# nuc972_power.net
KiCad netlist of a schematic drawn in Altium Designer
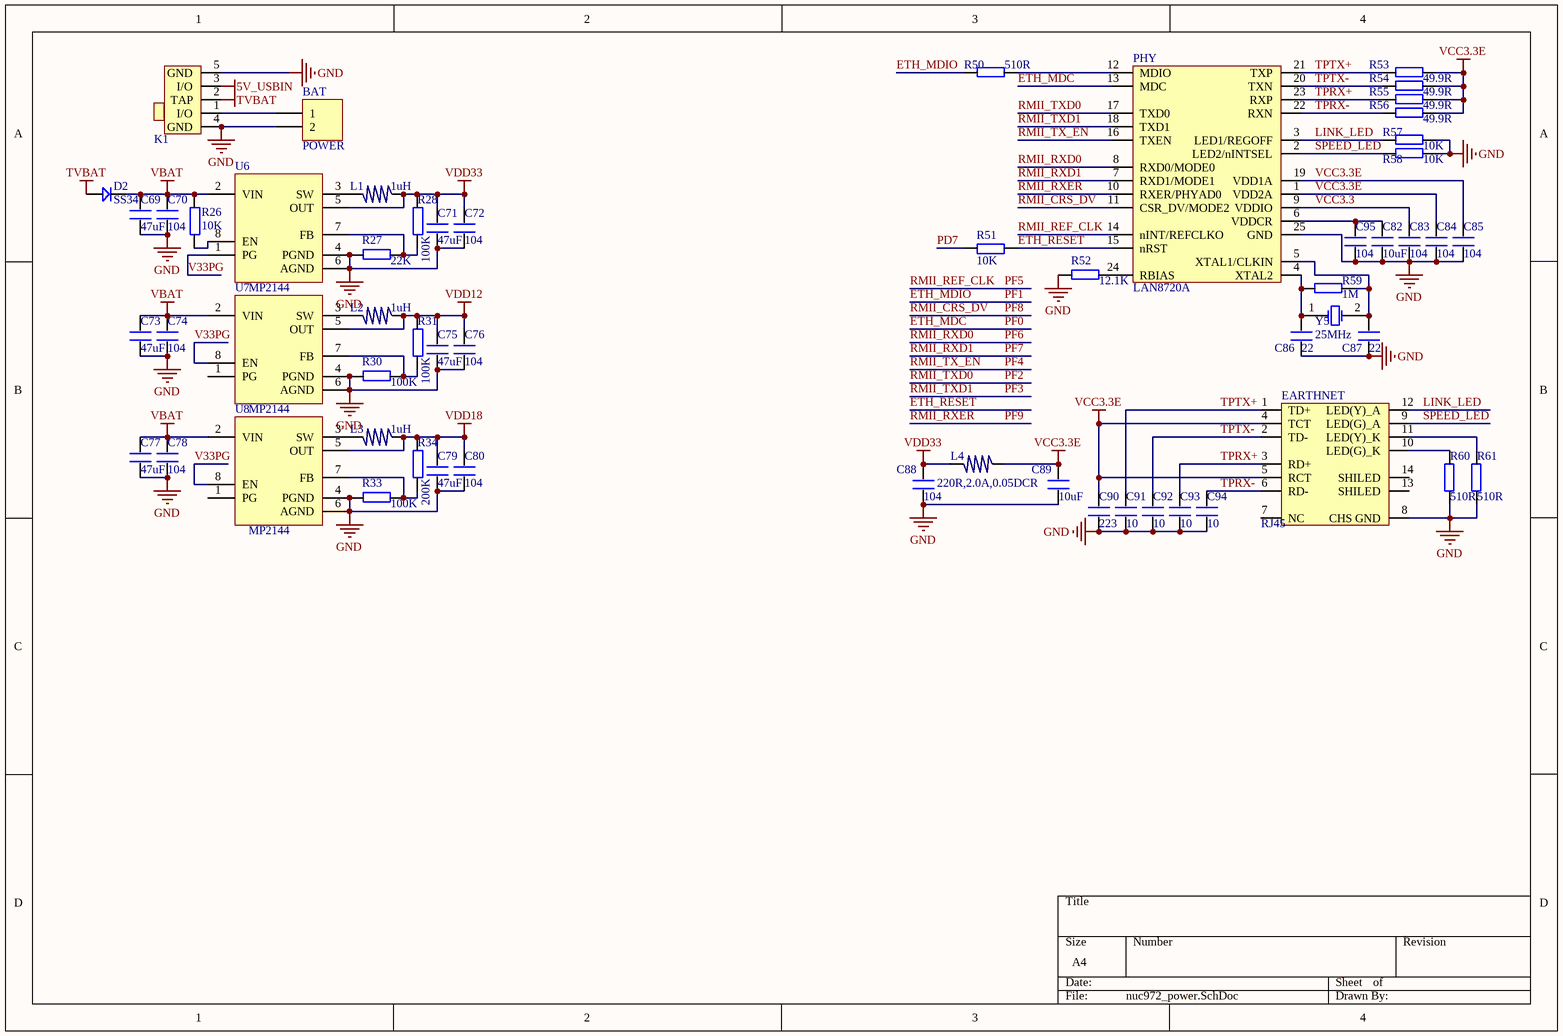
[diagram p0: nuc972_power.SchDoc]

(export (version "E")
  (design (tool "Eeschema 10.0.6"))
  (components
    (comp (ref "BAT")
      (value "POWER")
      (footprint "HDR1X2")
      (description "Header, 2-Pin")
      (fields (field (name "PUBLISHER") "Altium Limited"))
      (libsource (lib "阿波罗STM32F4&F7底板封装库") (part "Header 2"))
    )
    (comp (ref "C69")
      (value "47uF")
      (footprint "C 0805_L")
      (libsource (lib "阿波罗STM32F4&F7&H7底板封装库") (part "C"))
    )
    (comp (ref "C70")
      (value "104")
      (footprint "C 0603_L")
      (libsource (lib "阿波罗STM32F4&F7&H7底板封装库") (part "C"))
    )
    (comp (ref "C71")
      (value "47uF")
      (footprint "C 0805_L")
      (libsource (lib "阿波罗STM32F4&F7&H7底板封装库") (part "C"))
    )
    (comp (ref "C72")
      (value "104")
      (footprint "C 0603_L")
      (libsource (lib "阿波罗STM32F4&F7&H7底板封装库") (part "C"))
    )
    (comp (ref "C73")
      (value "47uF")
      (footprint "C 0805_L")
      (libsource (lib "阿波罗STM32F4&F7&H7底板封装库") (part "C"))
    )
    (comp (ref "C74")
      (value "104")
      (footprint "C 0603_L")
      (libsource (lib "阿波罗STM32F4&F7&H7底板封装库") (part "C"))
    )
    (comp (ref "C75")
      (value "47uF")
      (footprint "C 0805_L")
      (libsource (lib "阿波罗STM32F4&F7&H7底板封装库") (part "C"))
    )
    (comp (ref "C76")
      (value "104")
      (footprint "C 0603_L")
      (libsource (lib "阿波罗STM32F4&F7&H7底板封装库") (part "C"))
    )
    (comp (ref "C77")
      (value "47uF")
      (footprint "C 0805_L")
      (libsource (lib "阿波罗STM32F4&F7&H7底板封装库") (part "C"))
    )
    (comp (ref "C78")
      (value "104")
      (footprint "C 0603_L")
      (libsource (lib "阿波罗STM32F4&F7&H7底板封装库") (part "C"))
    )
    (comp (ref "C79")
      (value "47uF")
      (footprint "C 0805_L")
      (libsource (lib "阿波罗STM32F4&F7&H7底板封装库") (part "C"))
    )
    (comp (ref "C80")
      (value "104")
      (footprint "C 0603_L")
      (libsource (lib "阿波罗STM32F4&F7&H7底板封装库") (part "C"))
    )
    (comp (ref "C82") (value "10uF") (footprint "C 0603_L") (libsource (lib "ALIENTEK_COMPONENT") (part "C")))
    (comp (ref "C83") (value "104") (footprint "C 0603_L") (libsource (lib "MYCOMLIB") (part "C")))
    (comp (ref "C84") (value "104") (footprint "C 0603_L") (libsource (lib "MYCOMLIB") (part "C")))
    (comp (ref "C85") (value "104") (footprint "C 0603_L") (libsource (lib "MYCOMLIB") (part "C")))
    (comp (ref "C86") (value "22") (footprint "C 0603_L") (libsource (lib "MYCOMLIB") (part "C")))
    (comp (ref "C87") (value "22") (footprint "C 0603_L") (libsource (lib "MYCOMLIB") (part "C")))
    (comp (ref "C88") (value "104") (footprint "C 0603_L") (libsource (lib "ALIENTEK_COMPONENT") (part "C")))
    (comp (ref "C89") (value "10uF") (footprint "C 0603_L") (libsource (lib "ALIENTEK_COMPONENT") (part "C")))
    (comp (ref "C90") (value "223") (footprint "C 0603_L") (libsource (lib "MYCOMLIB") (part "C")))
    (comp (ref "C91") (value "10") (footprint "C 0603_L") (libsource (lib "MYCOMLIB") (part "C")))
    (comp (ref "C92") (value "10") (footprint "C 0603_L") (libsource (lib "MYCOMLIB") (part "C")))
    (comp (ref "C93") (value "10") (footprint "C 0603_L") (libsource (lib "MYCOMLIB") (part "C")))
    (comp (ref "C94") (value "10") (footprint "C 0603_L") (libsource (lib "MYCOMLIB") (part "C")))
    (comp (ref "C95") (value "104") (footprint "C 0603_L") (libsource (lib "MYCOMLIB") (part "C")))
    (comp (ref "D2") (value "SS34") (footprint "SMA") (libsource (lib "阿波罗STM32F4&F7&H7底板封装库") (part "D")))
    (comp (ref "EARTHNET")
      (value "RJ45")
      (footprint "RJ-45A12")
      (libsource (lib "MYCOMLIB") (part "HR911105"))
    )
    (comp (ref "K1")
      (value "BUTTON_DIP3")
      (footprint "BTN8.8*4.6")
      (description "拨动开关SS-12F44")
      (libsource (lib "Pandora_STM32L4_Board_V2.4") (part "BUTTON_DIP3"))
    )
    (comp (ref "L1") (value "1uH") (footprint "NR3015") (libsource (lib "MiniFly ") (part "L")))
    (comp (ref "L2") (value "1uH") (footprint "NR3015") (libsource (lib "MiniFly ") (part "L")))
    (comp (ref "L3") (value "1uH") (footprint "NR3015") (libsource (lib "MiniFly ") (part "L")))
    (comp (ref "L4")
      (value "220R,2.0A,0.05DCR")
      (footprint "L 0603")
      (libsource (lib "ALIENTEK_COMPONENT") (part "L"))
    )
    (comp (ref "PHY")
      (value "LAN8720A")
      (footprint "QFN24 4x4_N")
      (description "ETH PHY")
      (libsource (lib "ALIENTEK_COMPONENT") (part "LAN8720"))
    )
    (comp (ref "R26") (value "10K") (footprint "R 0603_L") (libsource (lib "阿波罗STM32F4&F7底板封装库") (part "R")))
    (comp (ref "R27") (value "22K") (footprint "R 0603_L") (libsource (lib "阿波罗STM32F4&F7底板封装库") (part "R")))
    (comp (ref "R28") (value "100K") (footprint "R 0603_L") (libsource (lib "阿波罗STM32F4&F7底板封装库") (part "R")))
    (comp (ref "R30") (value "100K") (footprint "R 0603_L") (libsource (lib "阿波罗STM32F4&F7底板封装库") (part "R")))
    (comp (ref "R31") (value "100K") (footprint "R 0603_L") (libsource (lib "阿波罗STM32F4&F7底板封装库") (part "R")))
    (comp (ref "R33") (value "100K") (footprint "R 0603_L") (libsource (lib "阿波罗STM32F4&F7底板封装库") (part "R")))
    (comp (ref "R34") (value "200K") (footprint "R 0603_L") (libsource (lib "阿波罗STM32F4&F7底板封装库") (part "R")))
    (comp (ref "R50") (value "510R") (footprint "R 0603_L") (libsource (lib "MYCOMLIB") (part "R")))
    (comp (ref "R51") (value "10K") (footprint "R 0603_L") (libsource (lib "MYCOMLIB") (part "R")))
    (comp (ref "R52") (value "12.1K") (footprint "R 0603_L") (libsource (lib "MYCOMLIB") (part "R")))
    (comp (ref "R53") (value "49.9R") (footprint "R 0603_L") (libsource (lib "MYCOMLIB") (part "R")))
    (comp (ref "R54") (value "49.9R") (footprint "R 0603_L") (libsource (lib "MYCOMLIB") (part "R")))
    (comp (ref "R55") (value "49.9R") (footprint "R 0603_L") (libsource (lib "MYCOMLIB") (part "R")))
    (comp (ref "R56") (value "49.9R") (footprint "R 0603_L") (libsource (lib "MYCOMLIB") (part "R")))
    (comp (ref "R57") (value "10K") (footprint "R 0603_L") (libsource (lib "MYCOMLIB") (part "R")))
    (comp (ref "R58") (value "10K") (footprint "R 0603_L") (libsource (lib "MYCOMLIB") (part "R")))
    (comp (ref "R59") (value "1M") (footprint "R 0603_L") (libsource (lib "MYCOMLIB") (part "R")))
    (comp (ref "R60") (value "510R") (footprint "R 0603_L") (libsource (lib "MYCOMLIB") (part "R")))
    (comp (ref "R61") (value "510R") (footprint "R 0603_L") (libsource (lib "MYCOMLIB") (part "R")))
    (comp (ref "U6") (value "MP2144") (footprint "SOT23-8L") (libsource (lib "LDO和DCDC") (part "MP2144")))
    (comp (ref "U7") (value "MP2144") (footprint "SOT23-8L") (libsource (lib "LDO和DCDC") (part "MP2144")))
    (comp (ref "U8") (value "MP2144") (footprint "SOT23-8L") (libsource (lib "LDO和DCDC") (part "MP2144")))
    (comp (ref "Y5")
      (value "25MHz")
      (footprint "OSC HC-49S")
      (description "Crystal Oscillator")
      (fields (field (name "PUBLISHER") "Altium Limited"))
      (libsource (lib "Miscellaneous Devices") (part "XTAL"))
    )
  )
  (nets
    (net (code "1") (name "/ETH_MDC") (class "Default")
      (node (ref "PHY") (pin "13") (pinfunction "MDC_13") (pintype "passive"))
    )
    (net (code "2") (name "/ETH_MDIO") (class "Default") (node (ref "R50") (pin "2") (pintype "passive")))
    (net (code "3") (name "/ETH_RESET") (class "Default")
      (node (ref "PHY") (pin "15") (pinfunction "nRST_15") (pintype "passive"))
      (node (ref "R51") (pin "2") (pintype "passive"))
    )
    (net (code "4") (name "/LINK_LED") (class "Default")
      (node (ref "EARTHNET") (pin "12") (pinfunction "LED(Y)_A_12") (pintype "passive"))
      (node (ref "PHY") (pin "3") (pinfunction "LED1/REGOFF_3") (pintype "passive"))
      (node (ref "R57") (pin "2") (pintype "passive"))
    )
    (net (code "5") (name "/PD7") (class "Default") (node (ref "R51") (pin "1") (pintype "passive")))
    (net (code "6") (name "/PF2") (class "Default")
      (node (ref "PHY") (pin "17") (pinfunction "TXD0_17") (pintype "passive"))
    )
    (net (code "7") (name "/PF3") (class "Default")
      (node (ref "PHY") (pin "18") (pinfunction "TXD1_18") (pintype "passive"))
    )
    (net (code "8") (name "/PF4") (class "Default")
      (node (ref "PHY") (pin "16") (pinfunction "TXEN_16") (pintype "passive"))
    )
    (net (code "9") (name "/PF5") (class "Default")
      (node (ref "PHY") (pin "14") (pinfunction "nINT/REFCLKO_14") (pintype "passive"))
    )
    (net (code "10") (name "/PF6") (class "Default")
      (node (ref "PHY") (pin "8") (pinfunction "RXD0/MODE0_8") (pintype "passive"))
    )
    (net (code "11") (name "/PF7") (class "Default")
      (node (ref "PHY") (pin "7") (pinfunction "RXD1/MODE1_7") (pintype "passive"))
    )
    (net (code "12") (name "/PF8") (class "Default")
      (node (ref "PHY") (pin "11") (pinfunction "CSR_DV/MODE2_11") (pintype "passive"))
    )
    (net (code "13") (name "/PF9") (class "Default")
      (node (ref "PHY") (pin "10") (pinfunction "RXER/PHYAD0_10") (pintype "passive"))
    )
    (net (code "14") (name "/SPEED_LED") (class "Default")
      (node (ref "EARTHNET") (pin "9") (pinfunction "LED(G)_A_9") (pintype "passive"))
      (node (ref "PHY") (pin "2") (pinfunction "LED2/nINTSEL_2") (pintype "passive"))
      (node (ref "R58") (pin "2") (pintype "passive"))
    )
    (net (code "15") (name "/TPRX+") (class "Default")
      (node (ref "C93") (pin "1") (pintype "passive"))
      (node (ref "EARTHNET") (pin "3") (pinfunction "RD+_3") (pintype "passive"))
      (node (ref "PHY") (pin "23") (pinfunction "RXP_23") (pintype "passive"))
      (node (ref "R55") (pin "2") (pintype "passive"))
    )
    (net (code "16") (name "/TPRX-") (class "Default")
      (node (ref "C94") (pin "1") (pintype "passive"))
      (node (ref "EARTHNET") (pin "6") (pinfunction "RD-_6") (pintype "passive"))
      (node (ref "PHY") (pin "22") (pinfunction "RXN_22") (pintype "passive"))
      (node (ref "R56") (pin "2") (pintype "passive"))
    )
    (net (code "17") (name "/TPTX+") (class "Default")
      (node (ref "C91") (pin "1") (pintype "passive"))
      (node (ref "EARTHNET") (pin "1") (pinfunction "TD+_1") (pintype "passive"))
      (node (ref "PHY") (pin "21") (pinfunction "TXP_21") (pintype "passive"))
      (node (ref "R53") (pin "2") (pintype "passive"))
    )
    (net (code "18") (name "/TPTX-") (class "Default")
      (node (ref "C92") (pin "1") (pintype "passive"))
      (node (ref "EARTHNET") (pin "2") (pinfunction "TD-_2") (pintype "passive"))
      (node (ref "PHY") (pin "20") (pinfunction "TXN_20") (pintype "passive"))
      (node (ref "R54") (pin "2") (pintype "passive"))
    )
    (net (code "19") (name "/V33PG") (class "Default")
      (node (ref "U6") (pin "1") (pinfunction "PG_1") (pintype "passive"))
      (node (ref "U7") (pin "8") (pinfunction "EN_8") (pintype "passive"))
      (node (ref "U8") (pin "8") (pinfunction "EN_8") (pintype "passive"))
    )
    (net (code "20") (name "/VCC3.3") (class "Default")
      (node (ref "C83") (pin "1") (pintype "passive"))
      (node (ref "PHY") (pin "9") (pinfunction "VDDIO_9") (pintype "passive"))
    )
    (net (code "21") (name "5V_USBIN") (class "Default")
      (node (ref "K1") (pin "3") (pinfunction "I/O_3") (pintype "passive"))
    )
    (net (code "22") (name "GND") (class "Default")
      (node (ref "BAT") (pin "2") (pinfunction "2_2") (pintype "passive"))
      (node (ref "C69") (pin "1") (pintype "passive"))
      (node (ref "C70") (pin "1") (pintype "passive"))
      (node (ref "C71") (pin "1") (pintype "passive"))
      (node (ref "C72") (pin "1") (pintype "passive"))
      (node (ref "C73") (pin "1") (pintype "passive"))
      (node (ref "C74") (pin "1") (pintype "passive"))
      (node (ref "C75") (pin "1") (pintype "passive"))
      (node (ref "C76") (pin "1") (pintype "passive"))
      (node (ref "C77") (pin "1") (pintype "passive"))
      (node (ref "C78") (pin "1") (pintype "passive"))
      (node (ref "C79") (pin "1") (pintype "passive"))
      (node (ref "C80") (pin "1") (pintype "passive"))
      (node (ref "C82") (pin "1") (pintype "passive"))
      (node (ref "C83") (pin "2") (pintype "passive"))
      (node (ref "C84") (pin "2") (pintype "passive"))
      (node (ref "C85") (pin "2") (pintype "passive"))
      (node (ref "C86") (pin "2") (pintype "passive"))
      (node (ref "C87") (pin "2") (pintype "passive"))
      (node (ref "C88") (pin "2") (pintype "passive"))
      (node (ref "C89") (pin "2") (pintype "passive"))
      (node (ref "C90") (pin "2") (pintype "passive"))
      (node (ref "C91") (pin "2") (pintype "passive"))
      (node (ref "C92") (pin "2") (pintype "passive"))
      (node (ref "C93") (pin "2") (pintype "passive"))
      (node (ref "C94") (pin "2") (pintype "passive"))
      (node (ref "C95") (pin "2") (pintype "passive"))
      (node (ref "EARTHNET") (pin "8") (pinfunction "CHS_GND_8") (pintype "passive"))
      (node (ref "K1") (pin "4") (pinfunction "GND_4") (pintype "passive"))
      (node (ref "K1") (pin "5") (pinfunction "GND_5") (pintype "passive"))
      (node (ref "PHY") (pin "25") (pinfunction "GND_25") (pintype "passive"))
      (node (ref "R27") (pin "2") (pintype "passive"))
      (node (ref "R30") (pin "2") (pintype "passive"))
      (node (ref "R33") (pin "2") (pintype "passive"))
      (node (ref "R52") (pin "2") (pintype "passive"))
      (node (ref "R57") (pin "1") (pintype "passive"))
      (node (ref "R58") (pin "1") (pintype "passive"))
      (node (ref "R60") (pin "2") (pintype "passive"))
      (node (ref "R61") (pin "2") (pintype "passive"))
      (node (ref "U6") (pin "4") (pinfunction "PGND_4") (pintype "passive"))
      (node (ref "U6") (pin "6") (pinfunction "AGND_6") (pintype "passive"))
      (node (ref "U7") (pin "4") (pinfunction "PGND_4") (pintype "passive"))
      (node (ref "U7") (pin "6") (pinfunction "AGND_6") (pintype "passive"))
      (node (ref "U8") (pin "4") (pinfunction "PGND_4") (pintype "passive"))
      (node (ref "U8") (pin "6") (pinfunction "AGND_6") (pintype "passive"))
    )
    (net (code "23") (name "Net-(BAT-Pad1)") (class "Default")
      (node (ref "BAT") (pin "1") (pinfunction "1_1") (pintype "passive"))
      (node (ref "K1") (pin "1") (pinfunction "I/O_1") (pintype "passive"))
    )
    (net (code "24") (name "Net-(EARTHNET-LED(G)_K)") (class "Default")
      (node (ref "EARTHNET") (pin "10") (pinfunction "LED(G)_K_10") (pintype "passive"))
      (node (ref "R60") (pin "1") (pintype "passive"))
    )
    (net (code "25") (name "Net-(EARTHNET-LED(Y)_K)") (class "Default")
      (node (ref "EARTHNET") (pin "11") (pinfunction "LED(Y)_K_11") (pintype "passive"))
      (node (ref "R61") (pin "1") (pintype "passive"))
    )
    (net (code "26") (name "Net-(PHY-MDIO)") (class "Default")
      (node (ref "PHY") (pin "12") (pinfunction "MDIO_12") (pintype "passive"))
      (node (ref "R50") (pin "1") (pintype "passive"))
    )
    (net (code "27") (name "Net-(PHY-RBIAS)") (class "Default")
      (node (ref "PHY") (pin "24") (pinfunction "RBIAS_24") (pintype "passive"))
      (node (ref "R52") (pin "1") (pintype "passive"))
    )
    (net (code "28") (name "Net-(PHY-VDDCR)") (class "Default")
      (node (ref "C82") (pin "2") (pintype "passive"))
      (node (ref "C95") (pin "1") (pintype "passive"))
      (node (ref "PHY") (pin "6") (pinfunction "VDDCR_6") (pintype "passive"))
    )
    (net (code "29") (name "Net-(PHY-XTAL1{slash}CLKIN)") (class "Default")
      (node (ref "C87") (pin "1") (pintype "passive"))
      (node (ref "PHY") (pin "5") (pinfunction "XTAL1/CLKIN_5") (pintype "passive"))
      (node (ref "R59") (pin "1") (pintype "passive"))
      (node (ref "Y5") (pin "2") (pinfunction "OSC2_2") (pintype "passive"))
    )
    (net (code "30") (name "Net-(PHY-XTAL2)") (class "Default")
      (node (ref "C86") (pin "1") (pintype "passive"))
      (node (ref "PHY") (pin "4") (pinfunction "XTAL2_4") (pintype "passive"))
      (node (ref "R59") (pin "2") (pintype "passive"))
      (node (ref "Y5") (pin "1") (pinfunction "OSC1_1") (pintype "passive"))
    )
    (net (code "31") (name "Net-(U6-EN)") (class "Default")
      (node (ref "R26") (pin "1") (pintype "passive"))
      (node (ref "U6") (pin "8") (pinfunction "EN_8") (pintype "passive"))
    )
    (net (code "32") (name "Net-(U6-FB)") (class "Default")
      (node (ref "R27") (pin "1") (pintype "passive"))
      (node (ref "R28") (pin "1") (pintype "passive"))
      (node (ref "U6") (pin "7") (pinfunction "FB_7") (pintype "passive"))
    )
    (net (code "33") (name "Net-(U6-SW)") (class "Default")
      (node (ref "L1") (pin "2") (pintype "passive"))
      (node (ref "U6") (pin "3") (pinfunction "SW_3") (pintype "passive"))
    )
    (net (code "34") (name "Net-(U7-FB)") (class "Default")
      (node (ref "R30") (pin "1") (pintype "passive"))
      (node (ref "R31") (pin "1") (pintype "passive"))
      (node (ref "U7") (pin "7") (pinfunction "FB_7") (pintype "passive"))
    )
    (net (code "35") (name "Net-(U7-SW)") (class "Default")
      (node (ref "L2") (pin "2") (pintype "passive"))
      (node (ref "U7") (pin "3") (pinfunction "SW_3") (pintype "passive"))
    )
    (net (code "36") (name "Net-(U8-FB)") (class "Default")
      (node (ref "R33") (pin "1") (pintype "passive"))
      (node (ref "R34") (pin "1") (pintype "passive"))
      (node (ref "U8") (pin "7") (pinfunction "FB_7") (pintype "passive"))
    )
    (net (code "37") (name "Net-(U8-SW)") (class "Default")
      (node (ref "L3") (pin "2") (pintype "passive"))
      (node (ref "U8") (pin "3") (pinfunction "SW_3") (pintype "passive"))
    )
    (net (code "38") (name "TVBAT") (class "Default")
      (node (ref "D2") (pin "1") (pintype "passive"))
      (node (ref "K1") (pin "2") (pinfunction "TAP_2") (pintype "passive"))
    )
    (net (code "39") (name "VBAT") (class "Default")
      (node (ref "C69") (pin "2") (pintype "passive"))
      (node (ref "C70") (pin "2") (pintype "passive"))
      (node (ref "C73") (pin "2") (pintype "passive"))
      (node (ref "C74") (pin "2") (pintype "passive"))
      (node (ref "C77") (pin "2") (pintype "passive"))
      (node (ref "C78") (pin "2") (pintype "passive"))
      (node (ref "D2") (pin "2") (pintype "passive"))
      (node (ref "R26") (pin "2") (pintype "passive"))
      (node (ref "U6") (pin "2") (pinfunction "VIN_2") (pintype "passive"))
      (node (ref "U7") (pin "2") (pinfunction "VIN_2") (pintype "passive"))
      (node (ref "U8") (pin "2") (pinfunction "VIN_2") (pintype "passive"))
    )
    (net (code "40") (name "VCC3.3E") (class "Default")
      (node (ref "C84") (pin "1") (pintype "passive"))
      (node (ref "C85") (pin "1") (pintype "passive"))
      (node (ref "C89") (pin "1") (pintype "passive"))
      (node (ref "C90") (pin "1") (pintype "passive"))
      (node (ref "EARTHNET") (pin "4") (pinfunction "TCT_4") (pintype "passive"))
      (node (ref "EARTHNET") (pin "5") (pinfunction "RCT_5") (pintype "passive"))
      (node (ref "L4") (pin "1") (pintype "passive"))
      (node (ref "PHY") (pin "1") (pinfunction "VDD2A_1") (pintype "passive"))
      (node (ref "PHY") (pin "19") (pinfunction "VDD1A_19") (pintype "passive"))
      (node (ref "R53") (pin "1") (pintype "passive"))
      (node (ref "R54") (pin "1") (pintype "passive"))
      (node (ref "R55") (pin "1") (pintype "passive"))
      (node (ref "R56") (pin "1") (pintype "passive"))
    )
    (net (code "41") (name "VDD12") (class "Default")
      (node (ref "C75") (pin "2") (pintype "passive"))
      (node (ref "C76") (pin "2") (pintype "passive"))
      (node (ref "L2") (pin "1") (pintype "passive"))
      (node (ref "R31") (pin "2") (pintype "passive"))
      (node (ref "U7") (pin "5") (pinfunction "OUT_5") (pintype "passive"))
    )
    (net (code "42") (name "VDD18") (class "Default")
      (node (ref "C79") (pin "2") (pintype "passive"))
      (node (ref "C80") (pin "2") (pintype "passive"))
      (node (ref "L3") (pin "1") (pintype "passive"))
      (node (ref "R34") (pin "2") (pintype "passive"))
      (node (ref "U8") (pin "5") (pinfunction "OUT_5") (pintype "passive"))
    )
    (net (code "43") (name "VDD33") (class "Default")
      (node (ref "C71") (pin "2") (pintype "passive"))
      (node (ref "C72") (pin "2") (pintype "passive"))
      (node (ref "C88") (pin "1") (pintype "passive"))
      (node (ref "L1") (pin "1") (pintype "passive"))
      (node (ref "L4") (pin "2") (pintype "passive"))
      (node (ref "R28") (pin "2") (pintype "passive"))
      (node (ref "U6") (pin "5") (pinfunction "OUT_5") (pintype "passive"))
    )
    (net (code "44") (name "unconnected-(EARTHNET-NC-Pad7)") (class "Default")
      (node (ref "EARTHNET") (pin "7") (pinfunction "NC_7") (pintype "passive"))
    )
    (net (code "45") (name "unconnected-(EARTHNET-SHILED-Pad13)") (class "Default")
      (node (ref "EARTHNET") (pin "13") (pinfunction "SHILED_13") (pintype "passive"))
    )
    (net (code "46") (name "unconnected-(EARTHNET-SHILED-Pad14)") (class "Default")
      (node (ref "EARTHNET") (pin "14") (pinfunction "SHILED_14") (pintype "passive"))
    )
    (net (code "47") (name "unconnected-(U7-PG-Pad1)") (class "Default")
      (node (ref "U7") (pin "1") (pinfunction "PG_1") (pintype "passive"))
    )
    (net (code "48") (name "unconnected-(U8-PG-Pad1)") (class "Default")
      (node (ref "U8") (pin "1") (pinfunction "PG_1") (pintype "passive"))
    )
  )
)
